# FDC.net
KiCad netlist of a schematic drawn in Altium Designer
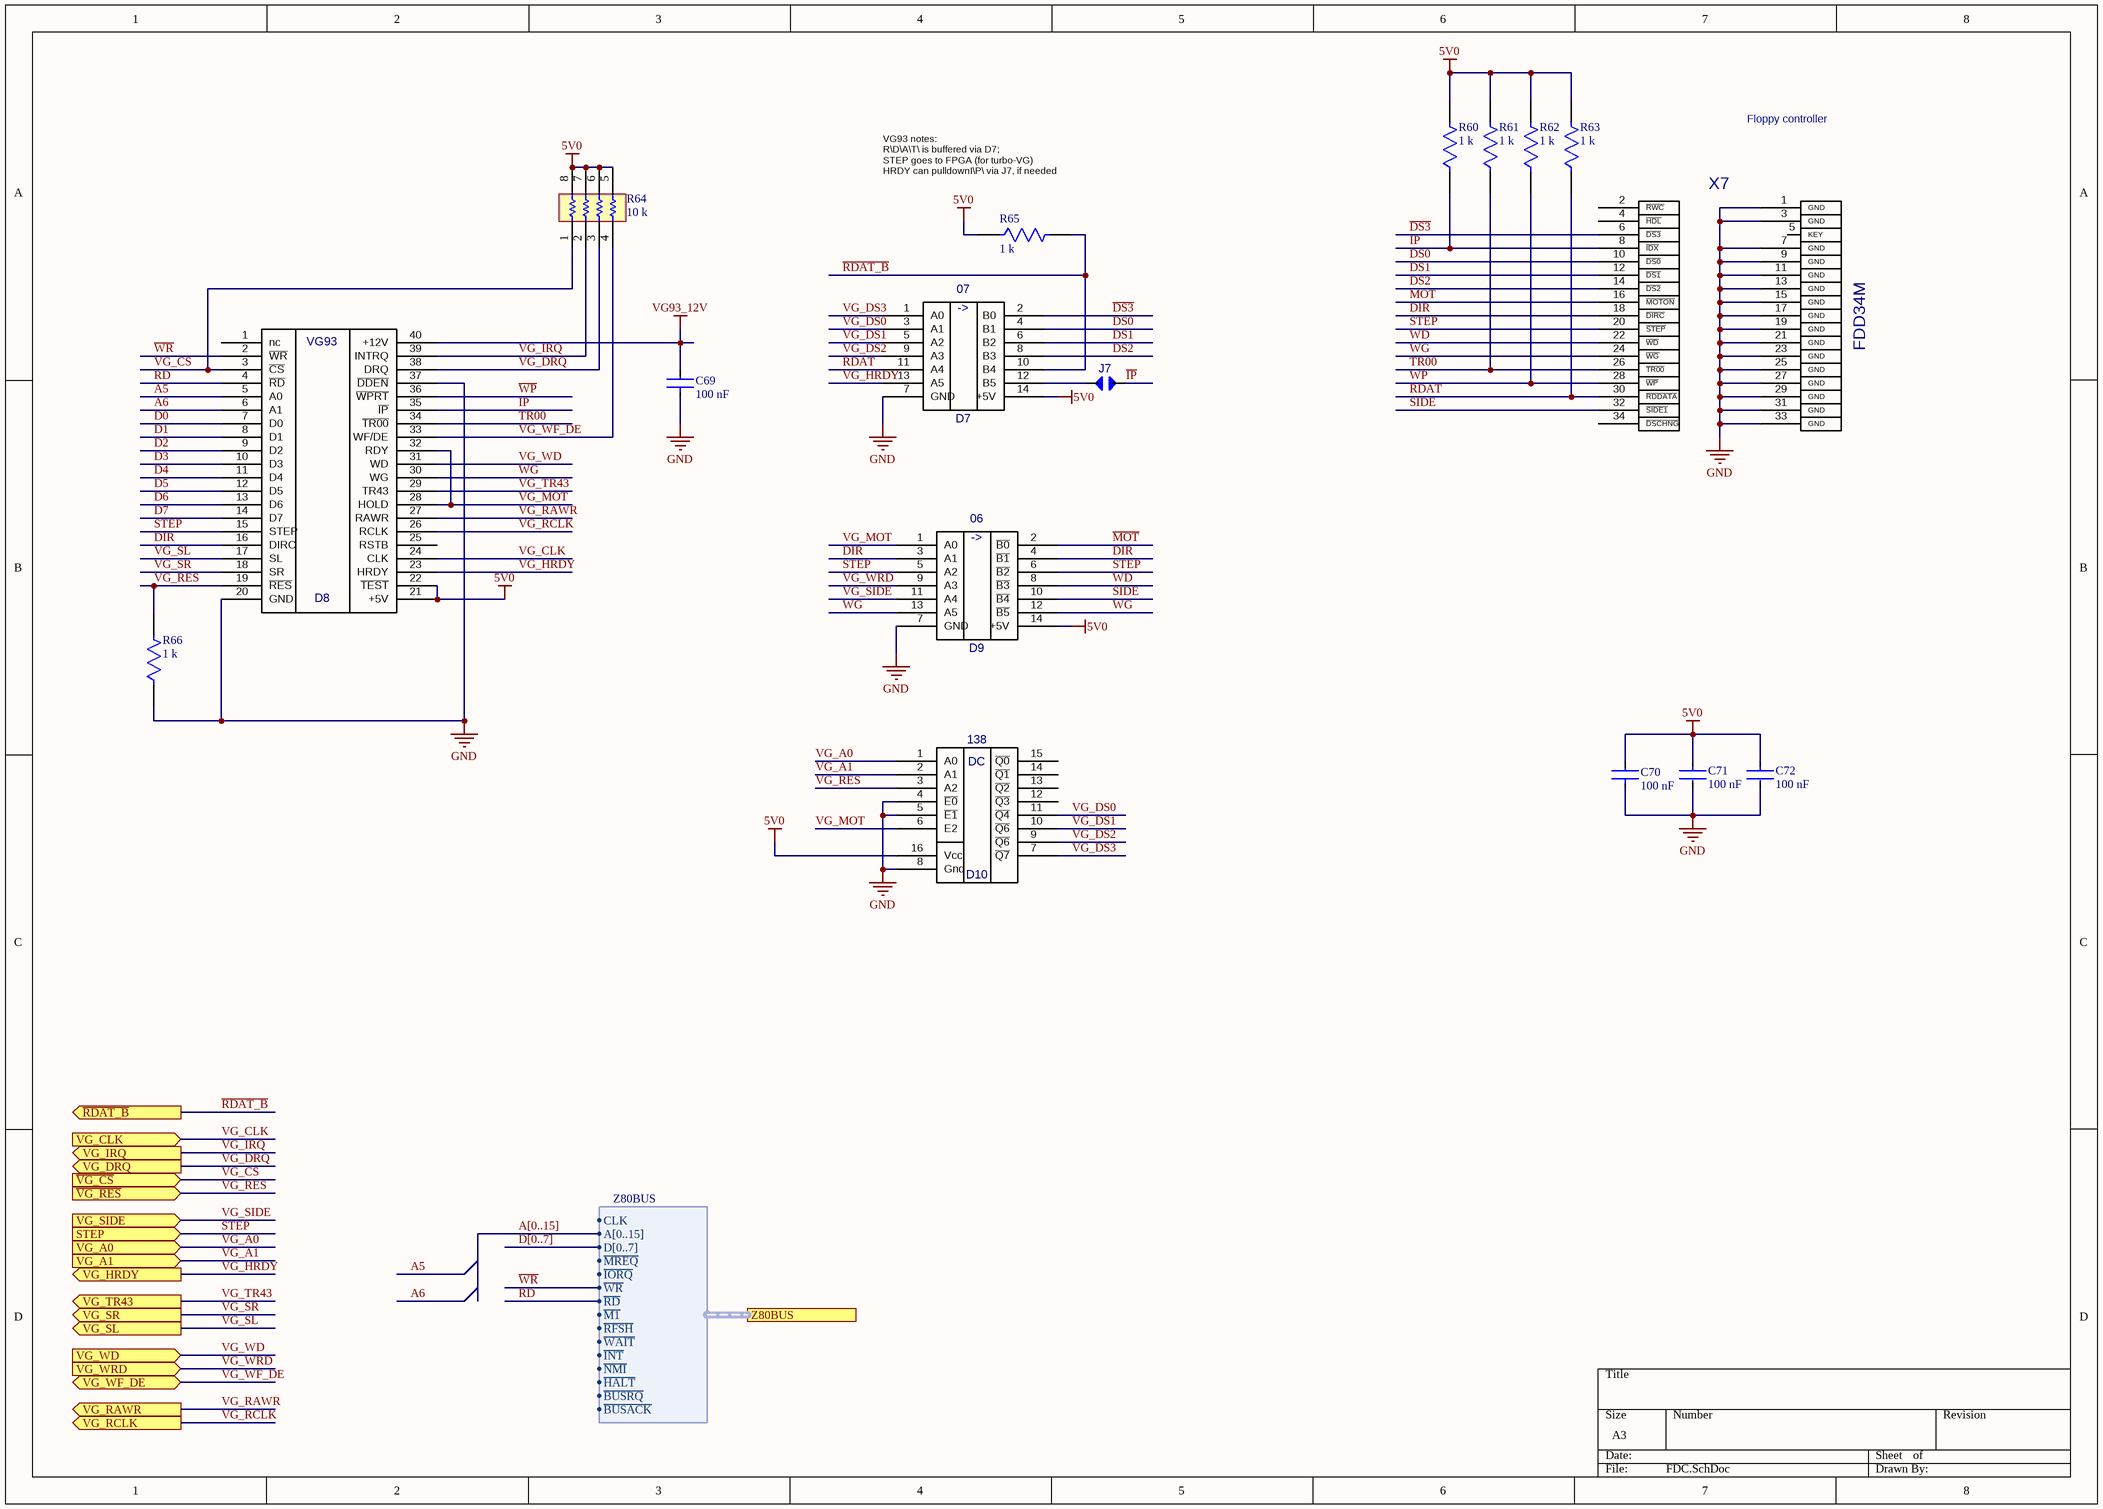
[diagram p0: FDC.SchDoc]

(export (version "E")
  (design (tool "Eeschema 10.0.6"))
  (components
    (comp (ref "C69")
      (value "CC0805-1.5pF")
      (footprint "CC0805")
      (description "CL21 Series 0805 1.5pF 50V ±0.25pF Tolerance C0G Multilayer Ceramic Chip Capacitor")
      (fields
        (field (name "MANUFACTURER PART NUMBER") "CL21C1R5CBANNNC")
        (field (name "CAPACITANCE") "100 nF")
        (field (name "MANUFACTURER") "Samsung")
      )
      (libsource (lib "zxevo") (part "CC0805"))
    )
    (comp (ref "C70")
      (value "CC0805-1.5pF")
      (footprint "CC0805")
      (description "CL21 Series 0805 1.5pF 50V ±0.25pF Tolerance C0G Multilayer Ceramic Chip Capacitor")
      (fields
        (field (name "MANUFACTURER PART NUMBER") "CL21C1R5CBANNNC")
        (field (name "CAPACITANCE") "100 nF")
        (field (name "MANUFACTURER") "Samsung")
      )
      (libsource (lib "zxevo") (part "CC0805"))
    )
    (comp (ref "C71")
      (value "CC0805-1.5pF")
      (footprint "CC0805")
      (description "CL21 Series 0805 1.5pF 50V ±0.25pF Tolerance C0G Multilayer Ceramic Chip Capacitor")
      (fields
        (field (name "MANUFACTURER PART NUMBER") "CL21C1R5CBANNNC")
        (field (name "CAPACITANCE") "100 nF")
        (field (name "MANUFACTURER") "Samsung")
      )
      (libsource (lib "zxevo") (part "CC0805"))
    )
    (comp (ref "C72")
      (value "CC0805-1.5pF")
      (footprint "CC0805")
      (description "CL21 Series 0805 1.5pF 50V ±0.25pF Tolerance C0G Multilayer Ceramic Chip Capacitor")
      (fields
        (field (name "MANUFACTURER PART NUMBER") "CL21C1R5CBANNNC")
        (field (name "CAPACITANCE") "100 nF")
        (field (name "MANUFACTURER") "Samsung")
      )
      (libsource (lib "zxevo") (part "CC0805"))
    )
    (comp (ref "D7") (value "07") (footprint "SO14") (libsource (lib "zxevo") (part "07")))
    (comp (ref "D8") (value "KR1818VG93") (footprint "DIP40") (libsource (lib "zxevo") (part "KR1818VG93")))
    (comp (ref "D9") (value "06") (footprint "SO14") (libsource (lib "zxevo") (part "06")))
    (comp (ref "D10") (value "138") (footprint "SO16") (libsource (lib "zxevo") (part "138")))
    (comp (ref "J7")
      (value "JUMPER")
      (footprint "JUMPER_JUMPER(Primary)")
      (description "HLT->~IP")
      (libsource (lib "zxevo") (part "JUMPER"))
    )
    (comp (ref "R60")
      (value "CR0805-51")
      (footprint "CR0805")
      (description "51Ω ±0.5% 0.1W 1/10W Chip Resistor 0805 (2012 Metric) Thin Film")
      (fields
        (field (name "RESISTANCE") "1 k")
        (field (name "MANUFACTURER") "Susumu")
        (field (name "MANUFACTURER PART NUMBER") "RR1220Q-510-D")
      )
      (libsource (lib "zxevo") (part "CR0805"))
    )
    (comp (ref "R61")
      (value "CR0805-51")
      (footprint "CR0805")
      (description "51Ω ±0.5% 0.1W 1/10W Chip Resistor 0805 (2012 Metric) Thin Film")
      (fields
        (field (name "RESISTANCE") "1 k")
        (field (name "MANUFACTURER") "Susumu")
        (field (name "MANUFACTURER PART NUMBER") "RR1220Q-510-D")
      )
      (libsource (lib "zxevo") (part "CR0805"))
    )
    (comp (ref "R62")
      (value "CR0805-51")
      (footprint "CR0805")
      (description "51Ω ±0.5% 0.1W 1/10W Chip Resistor 0805 (2012 Metric) Thin Film")
      (fields
        (field (name "RESISTANCE") "1 k")
        (field (name "MANUFACTURER") "Susumu")
        (field (name "MANUFACTURER PART NUMBER") "RR1220Q-510-D")
      )
      (libsource (lib "zxevo") (part "CR0805"))
    )
    (comp (ref "R63")
      (value "CR0805-51")
      (footprint "CR0805")
      (description "51Ω ±0.5% 0.1W 1/10W Chip Resistor 0805 (2012 Metric) Thin Film")
      (fields
        (field (name "RESISTANCE") "1 k")
        (field (name "MANUFACTURER") "Susumu")
        (field (name "MANUFACTURER PART NUMBER") "RR1220Q-510-D")
      )
      (libsource (lib "zxevo") (part "CR0805"))
    )
    (comp (ref "R64")
      (value "CAY16-103J4LF")
      (footprint "BOUR-CAY16-J4_V")
      (description "Chip Resistor Array, 10 KOhm, +/- 5%, 62.5 mW, -55 to 125 degC, 8-Pin SMD, RoHS, Tape and Reel")
      (fields (field (name "TOLERANCE") "1%") (field (name "RESISTANCE") "10 k"))
      (libsource (lib "Altium Content Vault") (part "RES-P-8"))
    )
    (comp (ref "R65")
      (value "CR0805-51")
      (footprint "CR0805")
      (description "51Ω ±0.5% 0.1W 1/10W Chip Resistor 0805 (2012 Metric) Thin Film")
      (fields
        (field (name "RESISTANCE") "1 k")
        (field (name "MANUFACTURER") "Susumu")
        (field (name "MANUFACTURER PART NUMBER") "RR1220Q-510-D")
      )
      (libsource (lib "zxevo") (part "CR0805"))
    )
    (comp (ref "R66")
      (value "CR0805-51")
      (footprint "CR0805")
      (description "51Ω ±0.5% 0.1W 1/10W Chip Resistor 0805 (2012 Metric) Thin Film")
      (fields
        (field (name "RESISTANCE") "1 k")
        (field (name "MANUFACTURER") "Susumu")
        (field (name "MANUFACTURER PART NUMBER") "RR1220Q-510-D")
      )
      (libsource (lib "zxevo") (part "CR0805"))
    )
    (comp (ref "X7") (value "FDD34M") (footprint "FDD34M") (libsource (lib "zxevo") (part "FDD34M")))
  )
  (nets
    (net (code "16") (name "/A5") (class "Default")
      (node (ref "D8") (pin "5") (pinfunction "A0_5") (pintype "passive"))
    )
    (net (code "17") (name "/A6") (class "Default")
      (node (ref "D8") (pin "6") (pinfunction "A1_6") (pintype "passive"))
    )
    (net (code "19") (name "/D0") (class "Default")
      (node (ref "D8") (pin "7") (pinfunction "D0_7") (pintype "passive"))
    )
    (net (code "20") (name "/D1") (class "Default")
      (node (ref "D8") (pin "8") (pinfunction "D1_8") (pintype "passive"))
    )
    (net (code "21") (name "/D2") (class "Default")
      (node (ref "D8") (pin "9") (pinfunction "D2_9") (pintype "passive"))
    )
    (net (code "22") (name "/D3") (class "Default")
      (node (ref "D8") (pin "10") (pinfunction "D3_10") (pintype "passive"))
    )
    (net (code "23") (name "/D4") (class "Default")
      (node (ref "D8") (pin "11") (pinfunction "D4_11") (pintype "passive"))
    )
    (net (code "24") (name "/D5") (class "Default")
      (node (ref "D8") (pin "12") (pinfunction "D5_12") (pintype "passive"))
    )
    (net (code "25") (name "/D6") (class "Default")
      (node (ref "D8") (pin "13") (pinfunction "D6_13") (pintype "passive"))
    )
    (net (code "26") (name "/D7") (class "Default")
      (node (ref "D8") (pin "14") (pinfunction "D7_14") (pintype "passive"))
    )
    (net (code "27") (name "/DIR") (class "Default")
      (node (ref "D8") (pin "16") (pinfunction "DIRC_16") (pintype "passive"))
      (node (ref "D9") (pin "3") (pinfunction "A1_3") (pintype "passive"))
    )
    (net (code "29") (name "/STEP") (class "Default")
      (node (ref "D8") (pin "15") (pinfunction "STEP_15") (pintype "passive"))
      (node (ref "D9") (pin "5") (pinfunction "A2_5") (pintype "passive"))
    )
    (net (code "30") (name "/VG_A0") (class "Default")
      (node (ref "D10") (pin "1") (pinfunction "A0_1") (pintype "passive"))
    )
    (net (code "31") (name "/VG_A1") (class "Default")
      (node (ref "D10") (pin "2") (pinfunction "A1_2") (pintype "passive"))
    )
    (net (code "32") (name "/VG_CLK") (class "Default")
      (node (ref "D8") (pin "24") (pinfunction "CLK_24") (pintype "passive"))
    )
    (net (code "33") (name "/VG_DRQ") (class "Default")
      (node (ref "D8") (pin "38") (pinfunction "DRQ_38") (pintype "passive"))
      (node (ref "R64") (pin "3") (pinfunction "3_3") (pintype "passive"))
    )
    (net (code "34") (name "/VG_DS0") (class "Default")
      (node (ref "D10") (pin "11") (pinfunction "~{Q4}_11") (pintype "passive"))
      (node (ref "D7") (pin "3") (pinfunction "A1_3") (pintype "passive"))
    )
    (net (code "35") (name "/VG_DS1") (class "Default")
      (node (ref "D10") (pin "10") (pinfunction "~{Q6}_10") (pintype "passive"))
      (node (ref "D7") (pin "5") (pinfunction "A2_5") (pintype "passive"))
    )
    (net (code "36") (name "/VG_DS2") (class "Default")
      (node (ref "D10") (pin "9") (pinfunction "~{Q6}_9") (pintype "passive"))
      (node (ref "D7") (pin "9") (pinfunction "A3_9") (pintype "passive"))
    )
    (net (code "37") (name "/VG_DS3") (class "Default")
      (node (ref "D10") (pin "7") (pinfunction "~{Q7}_7") (pintype "passive"))
      (node (ref "D7") (pin "1") (pinfunction "A0_1") (pintype "passive"))
    )
    (net (code "38") (name "/VG_HRDY") (class "Default")
      (node (ref "D7") (pin "13") (pinfunction "A5_13") (pintype "passive"))
      (node (ref "D8") (pin "23") (pinfunction "HRDY_23") (pintype "passive"))
    )
    (net (code "39") (name "/VG_IRQ") (class "Default")
      (node (ref "D8") (pin "39") (pinfunction "INTRQ_39") (pintype "passive"))
      (node (ref "R64") (pin "2") (pinfunction "2_2") (pintype "passive"))
    )
    (net (code "40") (name "/VG_MOT") (class "Default")
      (node (ref "D10") (pin "6") (pinfunction "E2_6") (pintype "passive"))
      (node (ref "D8") (pin "28") (pinfunction "HOLD_28") (pintype "passive"))
      (node (ref "D8") (pin "32") (pinfunction "RDY_32") (pintype "passive"))
      (node (ref "D9") (pin "1") (pinfunction "A0_1") (pintype "passive"))
    )
    (net (code "41") (name "/VG_RAWR") (class "Default")
      (node (ref "D8") (pin "27") (pinfunction "RAWR_27") (pintype "passive"))
    )
    (net (code "42") (name "/VG_RCLK") (class "Default")
      (node (ref "D8") (pin "26") (pinfunction "RCLK_26") (pintype "passive"))
    )
    (net (code "43") (name "/VG_SIDE") (class "Default")
      (node (ref "D9") (pin "11") (pinfunction "A4_11") (pintype "passive"))
    )
    (net (code "44") (name "/VG_SL") (class "Default")
      (node (ref "D8") (pin "17") (pinfunction "SL_17") (pintype "passive"))
    )
    (net (code "45") (name "/VG_SR") (class "Default")
      (node (ref "D8") (pin "18") (pinfunction "SR_18") (pintype "passive"))
    )
    (net (code "46") (name "/VG_TR43") (class "Default")
      (node (ref "D8") (pin "29") (pinfunction "TR43_29") (pintype "passive"))
    )
    (net (code "47") (name "/VG_WD") (class "Default")
      (node (ref "D8") (pin "31") (pinfunction "WD_31") (pintype "passive"))
    )
    (net (code "48") (name "/VG_WF_DE") (class "Default")
      (node (ref "D8") (pin "33") (pinfunction "WF/DE_33") (pintype "passive"))
      (node (ref "R64") (pin "4") (pinfunction "4_4") (pintype "passive"))
    )
    (net (code "49") (name "/VG_WRD") (class "Default")
      (node (ref "D9") (pin "9") (pinfunction "A3_9") (pintype "passive"))
    )
    (net (code "50") (name "/WG") (class "Default")
      (node (ref "D8") (pin "30") (pinfunction "WG_30") (pintype "passive"))
      (node (ref "D9") (pin "13") (pinfunction "A5_13") (pintype "passive"))
    )
    (net (code "52") (name "/~{DIR}") (class "Default")
      (node (ref "D9") (pin "4") (pinfunction "~{B1}_4") (pintype "passive"))
      (node (ref "X7") (pin "18") (pinfunction "~{DIRC}_18") (pintype "passive"))
    )
    (net (code "53") (name "/~{DS0}") (class "Default")
      (node (ref "D7") (pin "4") (pinfunction "B1_4") (pintype "passive"))
      (node (ref "X7") (pin "10") (pinfunction "~{DS0}_10") (pintype "passive"))
    )
    (net (code "54") (name "/~{DS1}") (class "Default")
      (node (ref "D7") (pin "6") (pinfunction "B2_6") (pintype "passive"))
      (node (ref "X7") (pin "12") (pinfunction "~{DS1}_12") (pintype "passive"))
    )
    (net (code "55") (name "/~{DS2}") (class "Default")
      (node (ref "D7") (pin "8") (pinfunction "B3_8") (pintype "passive"))
      (node (ref "X7") (pin "14") (pinfunction "~{DS2}_14") (pintype "passive"))
    )
    (net (code "56") (name "/~{DS3}") (class "Default")
      (node (ref "D7") (pin "2") (pinfunction "B0_2") (pintype "passive"))
      (node (ref "X7") (pin "6") (pinfunction "~{DS3}_6") (pintype "passive"))
    )
    (net (code "57") (name "/~{IP}") (class "Default")
      (node (ref "D8") (pin "35") (pinfunction "~{IP}_35") (pintype "passive"))
      (node (ref "J7") (pin "1") (pinfunction "2_1") (pintype "passive"))
      (node (ref "R60") (pin "1") (pinfunction "1_1") (pintype "passive"))
      (node (ref "X7") (pin "8") (pinfunction "~{IDX}_8") (pintype "passive"))
    )
    (net (code "58") (name "/~{MOT}") (class "Default")
      (node (ref "D9") (pin "2") (pinfunction "~{B0}_2") (pintype "passive"))
      (node (ref "X7") (pin "16") (pinfunction "~{MOTON}_16") (pintype "passive"))
    )
    (net (code "59") (name "/~{RDAT_B}") (class "Default")
      (node (ref "D7") (pin "10") (pinfunction "B4_10") (pintype "passive"))
      (node (ref "R65") (pin "2") (pinfunction "2_2") (pintype "passive"))
    )
    (net (code "60") (name "/~{RDAT}") (class "Default")
      (node (ref "D7") (pin "11") (pinfunction "A4_11") (pintype "passive"))
      (node (ref "R63") (pin "1") (pinfunction "1_1") (pintype "passive"))
      (node (ref "X7") (pin "30") (pinfunction "~{RDDATA}_30") (pintype "passive"))
    )
    (net (code "61") (name "/~{RD}") (class "Default")
      (node (ref "D8") (pin "4") (pinfunction "~{RD}_4") (pintype "passive"))
    )
    (net (code "62") (name "/~{SIDE}") (class "Default")
      (node (ref "D9") (pin "10") (pinfunction "~{B4}_10") (pintype "passive"))
      (node (ref "X7") (pin "32") (pinfunction "~{SIDE1}_32") (pintype "passive"))
    )
    (net (code "63") (name "/~{STEP}") (class "Default")
      (node (ref "D9") (pin "6") (pinfunction "~{B2}_6") (pintype "passive"))
      (node (ref "X7") (pin "20") (pinfunction "~{STEP}_20") (pintype "passive"))
    )
    (net (code "64") (name "/~{TR00}") (class "Default")
      (node (ref "D8") (pin "34") (pinfunction "~{TR00}_34") (pintype "passive"))
      (node (ref "R61") (pin "1") (pinfunction "1_1") (pintype "passive"))
      (node (ref "X7") (pin "26") (pinfunction "~{TR00}_26") (pintype "passive"))
    )
    (net (code "65") (name "/~{VG_CS}") (class "Default")
      (node (ref "D8") (pin "3") (pinfunction "~{CS}_3") (pintype "passive"))
      (node (ref "R64") (pin "1") (pinfunction "1_1") (pintype "passive"))
    )
    (net (code "66") (name "/~{VG_RES}") (class "Default")
      (node (ref "D10") (pin "3") (pinfunction "A2_3") (pintype "passive"))
      (node (ref "D8") (pin "19") (pinfunction "~{RES}_19") (pintype "passive"))
      (node (ref "R66") (pin "2") (pinfunction "2_2") (pintype "passive"))
    )
    (net (code "67") (name "/~{WD}") (class "Default")
      (node (ref "D9") (pin "8") (pinfunction "~{B3}_8") (pintype "passive"))
      (node (ref "X7") (pin "22") (pinfunction "~{WD}_22") (pintype "passive"))
    )
    (net (code "68") (name "/~{WG}") (class "Default")
      (node (ref "D9") (pin "12") (pinfunction "~{B5}_12") (pintype "passive"))
      (node (ref "X7") (pin "24") (pinfunction "~{WG}_24") (pintype "passive"))
    )
    (net (code "69") (name "/~{WP}") (class "Default")
      (node (ref "D8") (pin "36") (pinfunction "~{WPRT}_36") (pintype "passive"))
      (node (ref "R62") (pin "1") (pinfunction "1_1") (pintype "passive"))
      (node (ref "X7") (pin "28") (pinfunction "~{WP}_28") (pintype "passive"))
    )
    (net (code "70") (name "/~{WR}") (class "Default")
      (node (ref "D8") (pin "2") (pinfunction "~{WR}_2") (pintype "passive"))
    )
    (net (code "71") (name "5V0") (class "Default")
      (node (ref "C70") (pin "2") (pinfunction "2_2") (pintype "passive"))
      (node (ref "C71") (pin "1") (pinfunction "1_1") (pintype "passive"))
      (node (ref "C72") (pin "1") (pinfunction "1_1") (pintype "passive"))
      (node (ref "D10") (pin "16") (pinfunction "Vcc_16") (pintype "passive"))
      (node (ref "D7") (pin "14") (pinfunction "+5V_14") (pintype "passive"))
      (node (ref "D8") (pin "21") (pinfunction "+5V_21") (pintype "passive"))
      (node (ref "D8") (pin "22") (pinfunction "~{TEST}_22") (pintype "passive"))
      (node (ref "D9") (pin "14") (pinfunction "+5V_14") (pintype "passive"))
      (node (ref "R60") (pin "2") (pinfunction "2_2") (pintype "passive"))
      (node (ref "R61") (pin "2") (pinfunction "2_2") (pintype "passive"))
      (node (ref "R62") (pin "2") (pinfunction "2_2") (pintype "passive"))
      (node (ref "R63") (pin "2") (pinfunction "2_2") (pintype "passive"))
      (node (ref "R64") (pin "5") (pinfunction "5_5") (pintype "passive"))
      (node (ref "R64") (pin "6") (pinfunction "6_6") (pintype "passive"))
      (node (ref "R64") (pin "7") (pinfunction "7_7") (pintype "passive"))
      (node (ref "R64") (pin "8") (pinfunction "8_8") (pintype "passive"))
      (node (ref "R65") (pin "1") (pinfunction "1_1") (pintype "passive"))
    )
    (net (code "72") (name "GND") (class "Default")
      (node (ref "C69") (pin "1") (pinfunction "1_1") (pintype "passive"))
      (node (ref "C70") (pin "1") (pinfunction "1_1") (pintype "passive"))
      (node (ref "C71") (pin "2") (pinfunction "2_2") (pintype "passive"))
      (node (ref "C72") (pin "2") (pinfunction "2_2") (pintype "passive"))
      (node (ref "D10") (pin "4") (pinfunction "~{E0}_4") (pintype "passive"))
      (node (ref "D10") (pin "5") (pinfunction "~{E1}_5") (pintype "passive"))
      (node (ref "D10") (pin "8") (pinfunction "Gnd_8") (pintype "passive"))
      (node (ref "D7") (pin "7") (pinfunction "GND_7") (pintype "passive"))
      (node (ref "D8") (pin "20") (pinfunction "GND_20") (pintype "passive"))
      (node (ref "D8") (pin "37") (pinfunction "~{DDEN}_37") (pintype "passive"))
      (node (ref "D9") (pin "7") (pinfunction "GND_7") (pintype "passive"))
      (node (ref "R66") (pin "1") (pinfunction "1_1") (pintype "passive"))
      (node (ref "X7") (pin "1") (pinfunction "GND_1") (pintype "passive"))
      (node (ref "X7") (pin "11") (pinfunction "GND_11") (pintype "passive"))
      (node (ref "X7") (pin "13") (pinfunction "GND_13") (pintype "passive"))
      (node (ref "X7") (pin "15") (pinfunction "GND_15") (pintype "passive"))
      (node (ref "X7") (pin "17") (pinfunction "GND_17") (pintype "passive"))
      (node (ref "X7") (pin "19") (pinfunction "GND_19") (pintype "passive"))
      (node (ref "X7") (pin "21") (pinfunction "GND_21") (pintype "passive"))
      (node (ref "X7") (pin "23") (pinfunction "GND_23") (pintype "passive"))
      (node (ref "X7") (pin "25") (pinfunction "GND_25") (pintype "passive"))
      (node (ref "X7") (pin "27") (pinfunction "GND_27") (pintype "passive"))
      (node (ref "X7") (pin "29") (pinfunction "GND_29") (pintype "passive"))
      (node (ref "X7") (pin "3") (pinfunction "GND_3") (pintype "passive"))
      (node (ref "X7") (pin "31") (pinfunction "GND_31") (pintype "passive"))
      (node (ref "X7") (pin "33") (pinfunction "GND_33") (pintype "passive"))
      (node (ref "X7") (pin "7") (pinfunction "GND_7") (pintype "passive"))
      (node (ref "X7") (pin "9") (pinfunction "GND_9") (pintype "passive"))
    )
    (net (code "73") (name "Net-(D7-B5)") (class "Default")
      (node (ref "D7") (pin "12") (pinfunction "B5_12") (pintype "passive"))
      (node (ref "J7") (pin "0") (pinfunction "1_0") (pintype "passive"))
    )
    (net (code "74") (name "VG93_12V") (class "Default")
      (node (ref "C69") (pin "2") (pinfunction "2_2") (pintype "passive"))
      (node (ref "D8") (pin "40") (pinfunction "+12V_40") (pintype "passive"))
    )
    (net (code "75") (name "unconnected-(D8-RSTB-Pad25)") (class "Default")
      (node (ref "D8") (pin "25") (pinfunction "RSTB_25") (pintype "passive"))
    )
    (net (code "76") (name "unconnected-(D8-nc-Pad1)") (class "Default")
      (node (ref "D8") (pin "1") (pinfunction "nc_1") (pintype "passive"))
    )
    (net (code "77") (name "unconnected-(D10-~{Q0}-Pad15)") (class "Default")
      (node (ref "D10") (pin "15") (pinfunction "~{Q0}_15") (pintype "passive"))
    )
    (net (code "78") (name "unconnected-(D10-~{Q1}-Pad14)") (class "Default")
      (node (ref "D10") (pin "14") (pinfunction "~{Q1}_14") (pintype "passive"))
    )
    (net (code "79") (name "unconnected-(D10-~{Q2}-Pad13)") (class "Default")
      (node (ref "D10") (pin "13") (pinfunction "~{Q2}_13") (pintype "passive"))
    )
    (net (code "80") (name "unconnected-(D10-~{Q3}-Pad12)") (class "Default")
      (node (ref "D10") (pin "12") (pinfunction "~{Q3}_12") (pintype "passive"))
    )
    (net (code "81") (name "unconnected-(X7-KEY-Pad5)") (class "Default")
      (node (ref "X7") (pin "5") (pinfunction "KEY_5") (pintype "passive"))
    )
    (net (code "82") (name "unconnected-(X7-~{DSCHNG}-Pad34)") (class "Default")
      (node (ref "X7") (pin "34") (pinfunction "~{DSCHNG}_34") (pintype "passive"))
    )
    (net (code "83") (name "unconnected-(X7-~{HDL}-Pad4)") (class "Default")
      (node (ref "X7") (pin "4") (pinfunction "~{HDL}_4") (pintype "passive"))
    )
    (net (code "84") (name "unconnected-(X7-~{RWC}-Pad2)") (class "Default")
      (node (ref "X7") (pin "2") (pinfunction "~{RWC}_2") (pintype "passive"))
    )
  )
)
